# roomba_main_pcb_v1.net
KiCad netlist of a schematic drawn in EAGLE
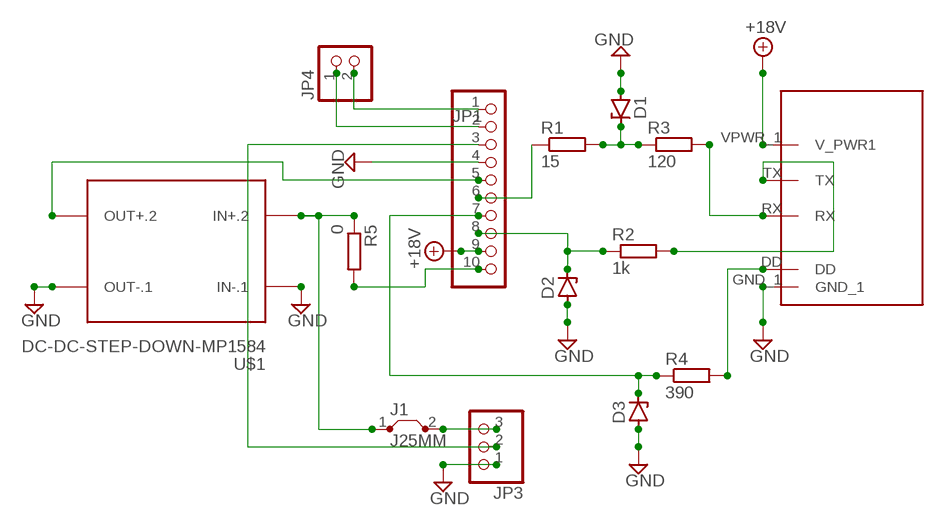
[diagram p0: schematic, sheet 1]

(export (version "E")
  (design (tool "Eeschema 10.0.6"))
  (components
    (comp (ref "D1")
      (value "ZENER-DIODESOD80C")
      (footprint "eagle-import:SOD80C")
      (libsource (lib "eagle-import") (part "ZENER-DIODESOD80C"))
    )
    (comp (ref "D2")
      (value "ZENER-DIODESOD80C")
      (footprint "eagle-import:SOD80C")
      (libsource (lib "eagle-import") (part "ZENER-DIODESOD80C"))
    )
    (comp (ref "D3")
      (value "ZENER-DIODESOD80C")
      (footprint "eagle-import:SOD80C")
      (libsource (lib "eagle-import") (part "ZENER-DIODESOD80C"))
    )
    (comp (ref "J1")
      (value "J25MM")
      (footprint "eagle-import:25")
      (libsource (lib "eagle-import") (part "J25MM"))
    )
    (comp (ref "JP1")
      (value "PINHD-1X10/90")
      (footprint "eagle-import:1X10_90")
      (libsource (lib "eagle-import") (part "PINHD-1X10/90"))
    )
    (comp (ref "JP3")
      (value "PINHD-1X3")
      (footprint "eagle-import:1X03")
      (libsource (lib "eagle-import") (part "PINHD-1X3"))
    )
    (comp (ref "JP4")
      (value "PINHD-1X2")
      (footprint "eagle-import:1X02")
      (libsource (lib "eagle-import") (part "PINHD-1X2"))
    )
    (comp (ref "R1")
      (value "15")
      (footprint "eagle-import:M1206")
      (libsource (lib "eagle-import") (part "R-EU_M1206"))
    )
    (comp (ref "R2")
      (value "1k")
      (footprint "eagle-import:M1206")
      (libsource (lib "eagle-import") (part "R-EU_M1206"))
    )
    (comp (ref "R3")
      (value "120")
      (footprint "eagle-import:M1206")
      (libsource (lib "eagle-import") (part "R-EU_M1206"))
    )
    (comp (ref "R4")
      (value "390")
      (footprint "eagle-import:M1206")
      (libsource (lib "eagle-import") (part "R-EU_M1206"))
    )
    (comp (ref "R5")
      (value "0")
      (footprint "eagle-import:M1206")
      (libsource (lib "eagle-import") (part "R-EU_M1206"))
    )
    (comp (ref "U$1")
      (value "DC-DC-STEP-DOWN-MP1584")
      (footprint "eagle-import:DC-DC-STEP-DOWN-MP1584")
      (libsource (lib "eagle-import") (part "DC-DC-STEP-DOWN-MP1584"))
    )
    (comp (ref "U$3")
      (value "7_PIN")
      (footprint "eagle-import:PIN-7")
      (libsource (lib "eagle-import") (part "7_PIN"))
    )
  )
  (nets
    (net (code "1") (name "+18V") (class "Default")
      (node (ref "JP1") (pin "9") (pinfunction "9_9") (pintype "passive"))
      (node (ref "U$3") (pin "VPWR_1") (pinfunction "V_PWR1_VPWR_1") (pintype "bidirectional"))
    )
    (net (code "2") (name "GND") (class "Default")
      (node (ref "D1") (pin "A") (pinfunction "A_A") (pintype "passive"))
      (node (ref "D2") (pin "A") (pinfunction "A_A") (pintype "passive"))
      (node (ref "D3") (pin "A") (pinfunction "A_A") (pintype "passive"))
      (node (ref "JP1") (pin "4") (pinfunction "4_4") (pintype "passive"))
      (node (ref "JP3") (pin "1") (pinfunction "1_1") (pintype "passive"))
      (node (ref "U$1") (pin "IN-.1") (pinfunction "IN-.1_IN-.1") (pintype "bidirectional"))
      (node (ref "U$1") (pin "OUT-.1") (pinfunction "OUT-.1_OUT-.1") (pintype "bidirectional"))
      (node (ref "U$3") (pin "GND_1") (pinfunction "GND_1_GND_1") (pintype "bidirectional"))
    )
    (net (code "3") (name "Net-(D1-PadC)") (class "Default")
      (node (ref "D1") (pin "C") (pinfunction "C_C") (pintype "passive"))
      (node (ref "R1") (pin "2") (pinfunction "2_2") (pintype "passive"))
      (node (ref "R3") (pin "1") (pinfunction "1_1") (pintype "passive"))
    )
    (net (code "4") (name "Net-(D2-PadC)") (class "Default")
      (node (ref "D2") (pin "C") (pinfunction "C_C") (pintype "passive"))
      (node (ref "JP1") (pin "8") (pinfunction "8_8") (pintype "passive"))
      (node (ref "R2") (pin "1") (pinfunction "1_1") (pintype "passive"))
    )
    (net (code "5") (name "Net-(D3-PadC)") (class "Default")
      (node (ref "D3") (pin "C") (pinfunction "C_C") (pintype "passive"))
      (node (ref "JP1") (pin "7") (pinfunction "7_7") (pintype "passive"))
      (node (ref "R4") (pin "1") (pinfunction "1_1") (pintype "passive"))
    )
    (net (code "6") (name "Net-(J1-Pad1)") (class "Default")
      (node (ref "J1") (pin "1") (pinfunction "1_1") (pintype "passive"))
      (node (ref "R5") (pin "1") (pinfunction "1_1") (pintype "passive"))
      (node (ref "U$1") (pin "IN+.2") (pinfunction "IN+.2_IN+.2") (pintype "bidirectional"))
    )
    (net (code "7") (name "Net-(J1-Pad2)") (class "Default")
      (node (ref "J1") (pin "2") (pinfunction "2_2") (pintype "passive"))
      (node (ref "JP3") (pin "3") (pinfunction "3_3") (pintype "passive"))
    )
    (net (code "8") (name "Net-(JP1-Pad1)") (class "Default")
      (node (ref "JP1") (pin "1") (pinfunction "1_1") (pintype "passive"))
      (node (ref "JP4") (pin "2") (pinfunction "2_2") (pintype "passive"))
    )
    (net (code "9") (name "Net-(JP1-Pad2)") (class "Default")
      (node (ref "JP1") (pin "2") (pinfunction "2_2") (pintype "passive"))
      (node (ref "JP4") (pin "1") (pinfunction "1_1") (pintype "passive"))
    )
    (net (code "10") (name "Net-(JP1-Pad3)") (class "Default")
      (node (ref "JP1") (pin "3") (pinfunction "3_3") (pintype "passive"))
      (node (ref "JP3") (pin "2") (pinfunction "2_2") (pintype "passive"))
    )
    (net (code "11") (name "Net-(JP1-Pad5)") (class "Default")
      (node (ref "JP1") (pin "5") (pinfunction "5_5") (pintype "passive"))
      (node (ref "U$1") (pin "OUT+.2") (pinfunction "OUT+.2_OUT+.2") (pintype "bidirectional"))
    )
    (net (code "12") (name "Net-(JP1-Pad6)") (class "Default")
      (node (ref "JP1") (pin "6") (pinfunction "6_6") (pintype "passive"))
      (node (ref "R1") (pin "1") (pinfunction "1_1") (pintype "passive"))
    )
    (net (code "13") (name "Net-(JP1-Pad10)") (class "Default")
      (node (ref "JP1") (pin "10") (pinfunction "10_10") (pintype "passive"))
      (node (ref "R5") (pin "2") (pinfunction "2_2") (pintype "passive"))
    )
    (net (code "14") (name "Net-(R2-Pad2)") (class "Default")
      (node (ref "R2") (pin "2") (pinfunction "2_2") (pintype "passive"))
      (node (ref "U$3") (pin "TX") (pinfunction "TX_TX") (pintype "bidirectional"))
    )
    (net (code "15") (name "Net-(R3-Pad2)") (class "Default")
      (node (ref "R3") (pin "2") (pinfunction "2_2") (pintype "passive"))
      (node (ref "U$3") (pin "RX") (pinfunction "RX_RX") (pintype "bidirectional"))
    )
    (net (code "16") (name "Net-(R4-Pad2)") (class "Default")
      (node (ref "R4") (pin "2") (pinfunction "2_2") (pintype "passive"))
      (node (ref "U$3") (pin "DD") (pinfunction "DD_DD") (pintype "bidirectional"))
    )
  )
)
